# TheStaticTurtle_oshw-sdi3g-fiber__schema.net
KiCad netlist of a schematic drawn in Altium Designer
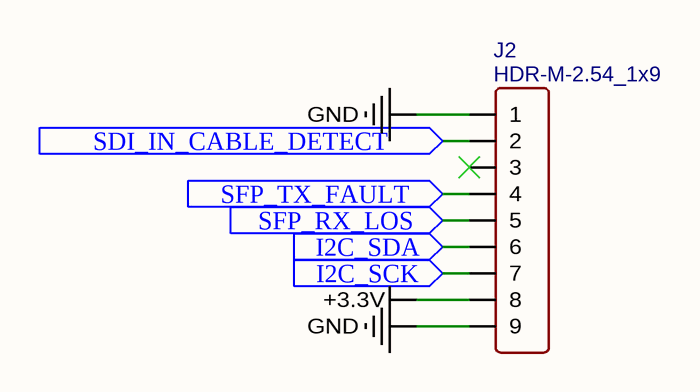
[diagram p0: TheStaticTurtle_oshw-sdi3g-fiber__schematic_V4-Normal_OSHW_BiDi_SDI_Fiber_Converter_V4_Normal_2024-11-17__Diag.schdoc]

(export (version "E")
  (design (tool "Eeschema 10.0.6"))
  (components
    (comp (ref "J2")
      (value "HDR-M-2.54_1x9")
      (fields (field (name "CONTRIBUTOR") "LCEDA_Lib"))
      (libsource (lib "altium-import") (part "root_0_HDR-M-2.54_1x9_"))
    )
  )
  (nets
    (net (code "1") (name "+3.3V") (class "Default")
      (node (ref "J2") (pin "8") (pinfunction "8_8") (pintype "passive"))
    )
    (net (code "2") (name "/I2C_SCK") (class "Default")
      (node (ref "J2") (pin "7") (pinfunction "7_7") (pintype "passive"))
    )
    (net (code "3") (name "/I2C_SDA") (class "Default")
      (node (ref "J2") (pin "6") (pinfunction "6_6") (pintype "passive"))
    )
    (net (code "4") (name "/SDI_IN_CABLE_DETECT") (class "Default")
      (node (ref "J2") (pin "2") (pinfunction "2_2") (pintype "passive"))
    )
    (net (code "5") (name "/SFP_RX_LOS") (class "Default")
      (node (ref "J2") (pin "5") (pinfunction "5_5") (pintype "passive"))
    )
    (net (code "6") (name "/SFP_TX_FAULT") (class "Default")
      (node (ref "J2") (pin "4") (pinfunction "4_4") (pintype "passive"))
    )
    (net (code "7") (name "GND") (class "Default")
      (node (ref "J2") (pin "1") (pinfunction "1_1") (pintype "passive"))
      (node (ref "J2") (pin "9") (pinfunction "9_9") (pintype "passive"))
    )
    (net (code "8") (name "unconnected-(J2-Pad3)") (class "Default")
      (node (ref "J2") (pin "3") (pinfunction "3_3") (pintype "passive+no_connect"))
    )
  )
)
